# AirSensor_LoRA.net
KiCad netlist of a schematic drawn in EAGLE
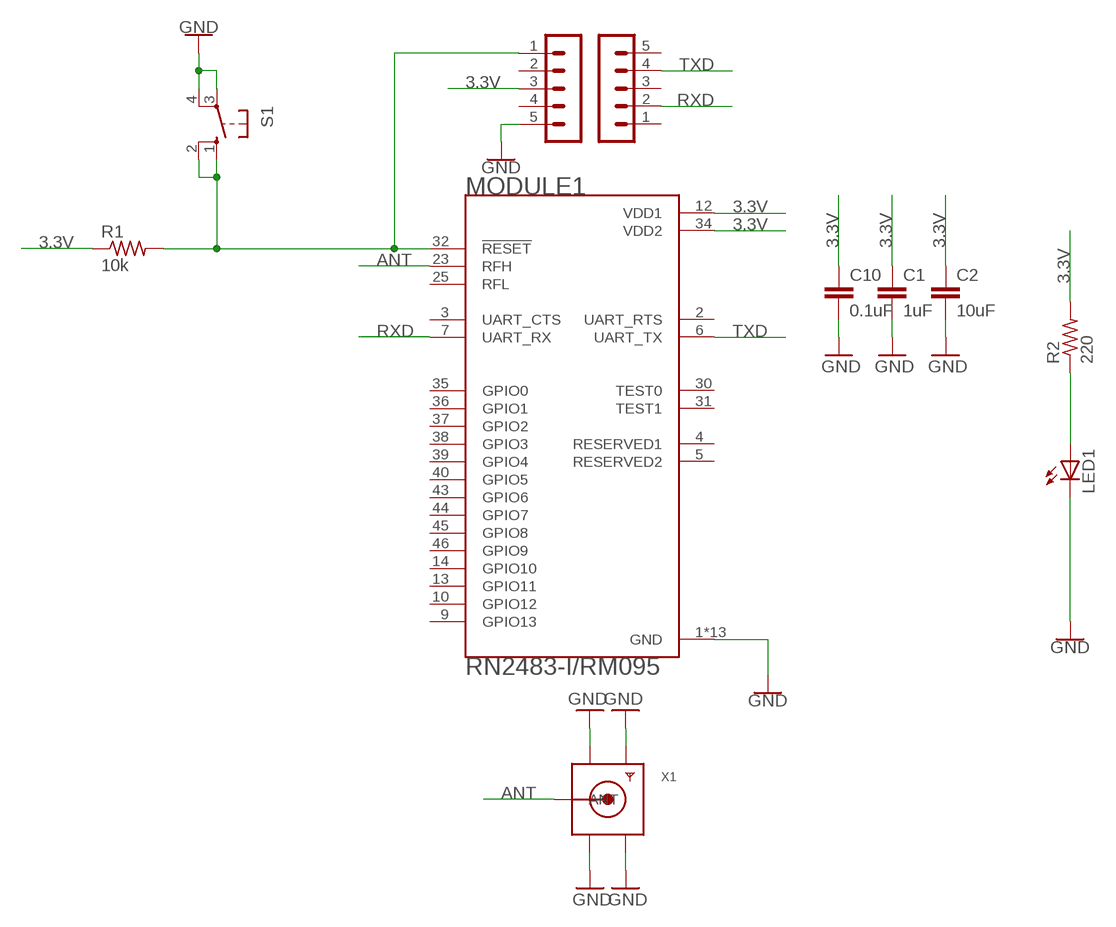
[diagram p0: schematic, sheet 1]

(export (version "E")
  (design (tool "Eeschema 10.0.6"))
  (components
    (comp (ref "C1")
      (value "1uF")
      (footprint "eagle-import:0805")
      (libsource (lib "eagle-import") (part "1.0UF-0805-25V-10%"))
    )
    (comp (ref "C2")
      (value "10uF")
      (footprint "eagle-import:0805")
      (libsource (lib "eagle-import") (part "1.0UF-0805-25V-10%"))
    )
    (comp (ref "C10")
      (value "0.1uF")
      (footprint "eagle-import:0805")
      (libsource (lib "eagle-import") (part "1.0UF-0805-25V-10%"))
    )
    (comp (ref "LED1")
      (value "LEDCHIPLED_0805")
      (footprint "eagle-import:CHIPLED_0805")
      (libsource (lib "eagle-import") (part "LEDCHIPLED_0805"))
    )
    (comp (ref "MODULE1")
      (value "RN2483-I/RM095")
      (footprint "eagle-import:MICROCHIP_RN2483-I_RM095")
      (fields (field (name "MF") "Microchip"))
      (libsource (lib "eagle-import") (part "RN2483-I/RM095"))
    )
    (comp (ref "R1")
      (value "10k")
      (footprint "eagle-import:RES_0805")
      (fields
        (field (name "DIGIKEY_PART_NUMBER") "541-0.0ATR-ND")
        (field (name "MANUFACTURER") "Vishay Dale")
        (field (name "MPN") "CRCW08050000Z0EA")
        (field (name "CREATED_BY") "PCBLayout.com")
      )
      (libsource (lib "eagle-import") (part "CRCW08050000Z0EA"))
    )
    (comp (ref "R2")
      (value "220")
      (footprint "eagle-import:RES_0805")
      (fields
        (field (name "DIGIKEY_PART_NUMBER") "541-0.0ATR-ND")
        (field (name "MANUFACTURER") "Vishay Dale")
        (field (name "MPN") "CRCW08050000Z0EA")
        (field (name "CREATED_BY") "PCBLayout.com")
      )
      (libsource (lib "eagle-import") (part "CRCW08050000Z0EA"))
    )
    (comp (ref "RFM95W_1")
      (value "LoRa_1")
      (footprint "eagle-import:MA05-1")
      (libsource (lib "eagle-import") (part "MA05-1"))
    )
    (comp (ref "RFM95W_2")
      (value "LoRa_2")
      (footprint "eagle-import:MA05-1")
      (libsource (lib "eagle-import") (part "MA05-1"))
    )
    (comp (ref "S1")
      (value "10-XX")
      (footprint "eagle-import:B3F-10XX")
      (fields (field (name "MPN") "B3F-1000"))
      (libsource (lib "eagle-import") (part "10-XX"))
    )
    (comp (ref "X1")
      (value "SMACONNECTOR_EDGE")
      (footprint "eagle-import:SMA_EDGELAUNCH")
      (libsource (lib "eagle-import") (part "SMACONNECTOR_EDGE"))
    )
  )
  (nets
    (net (code "1") (name "/3.3V") (class "Default")
      (node (ref "C1") (pin "1") (pinfunction "1_1") (pintype "passive"))
      (node (ref "C10") (pin "1") (pinfunction "1_1") (pintype "passive"))
      (node (ref "C2") (pin "1") (pinfunction "1_1") (pintype "passive"))
      (node (ref "MODULE1") (pin "12") (pinfunction "VDD1_12") (pintype "power_in"))
      (node (ref "MODULE1") (pin "34") (pinfunction "VDD2_34") (pintype "power_in"))
      (node (ref "R1") (pin "1") (pinfunction "1_1") (pintype "passive"))
      (node (ref "R2") (pin "2") (pinfunction "2_2") (pintype "passive"))
      (node (ref "RFM95W_1") (pin "3") (pinfunction "3_3") (pintype "passive"))
    )
    (net (code "2") (name "/ANT") (class "Default")
      (node (ref "MODULE1") (pin "23") (pinfunction "RFH_23") (pintype "input"))
      (node (ref "X1") (pin "P") (pinfunction "ANT_P") (pintype "bidirectional"))
    )
    (net (code "3") (name "/RXD") (class "Default")
      (node (ref "MODULE1") (pin "7") (pinfunction "UART_RX_7") (pintype "input"))
      (node (ref "RFM95W_2") (pin "2") (pinfunction "2_2") (pintype "passive"))
    )
    (net (code "4") (name "/TXD") (class "Default")
      (node (ref "MODULE1") (pin "6") (pinfunction "UART_TX_6") (pintype "output"))
      (node (ref "RFM95W_2") (pin "4") (pinfunction "4_4") (pintype "passive"))
    )
    (net (code "5") (name "GND") (class "Default")
      (node (ref "C1") (pin "2") (pinfunction "2_2") (pintype "passive"))
      (node (ref "C10") (pin "2") (pinfunction "2_2") (pintype "passive"))
      (node (ref "C2") (pin "2") (pinfunction "2_2") (pintype "passive"))
      (node (ref "LED1") (pin "C") (pinfunction "C_C") (pintype "passive"))
      (node (ref "MODULE1") (pin "1") (pinfunction "GND_1") (pintype "passive"))
      (node (ref "MODULE1") (pin "11") (pinfunction "GND_11") (pintype "passive"))
      (node (ref "MODULE1") (pin "20") (pinfunction "GND_20") (pintype "passive"))
      (node (ref "MODULE1") (pin "21") (pinfunction "GND_21") (pintype "passive"))
      (node (ref "MODULE1") (pin "22") (pinfunction "GND_22") (pintype "passive"))
      (node (ref "MODULE1") (pin "24") (pinfunction "GND_24") (pintype "passive"))
      (node (ref "MODULE1") (pin "26") (pinfunction "GND_26") (pintype "passive"))
      (node (ref "MODULE1") (pin "27") (pinfunction "GND_27") (pintype "passive"))
      (node (ref "MODULE1") (pin "28") (pinfunction "GND_28") (pintype "passive"))
      (node (ref "MODULE1") (pin "33") (pinfunction "GND_33") (pintype "passive"))
      (node (ref "MODULE1") (pin "41") (pinfunction "GND_41") (pintype "passive"))
      (node (ref "MODULE1") (pin "47") (pinfunction "GND_47") (pintype "passive"))
      (node (ref "MODULE1") (pin "8") (pinfunction "GND_8") (pintype "passive"))
      (node (ref "RFM95W_1") (pin "5") (pinfunction "5_5") (pintype "passive"))
      (node (ref "S1") (pin "3") (pinfunction "P_3") (pintype "passive"))
      (node (ref "S1") (pin "4") (pinfunction "P1_4") (pintype "passive"))
      (node (ref "X1") (pin "GND@1") (pinfunction "GND4_GND@1") (pintype "power_in"))
      (node (ref "X1") (pin "GND@2") (pinfunction "GND3_GND@2") (pintype "power_in"))
      (node (ref "X1") (pin "GND@3") (pinfunction "GND2_GND@3") (pintype "power_in"))
      (node (ref "X1") (pin "GND@4") (pinfunction "GND1_GND@4") (pintype "power_in"))
    )
    (net (code "6") (name "Net-(LED1-PadA)") (class "Default")
      (node (ref "LED1") (pin "A") (pinfunction "A_A") (pintype "passive"))
      (node (ref "R2") (pin "1") (pinfunction "1_1") (pintype "passive"))
    )
    (net (code "7") (name "Net-(MODULE1-~{RESET})") (class "Default")
      (node (ref "MODULE1") (pin "32") (pinfunction "~{RESET}_32") (pintype "input"))
      (node (ref "R1") (pin "2") (pinfunction "2_2") (pintype "passive"))
      (node (ref "RFM95W_1") (pin "1") (pinfunction "1_1") (pintype "passive"))
      (node (ref "S1") (pin "1") (pinfunction "S_1") (pintype "passive"))
      (node (ref "S1") (pin "2") (pinfunction "S1_2") (pintype "passive"))
    )
    (net (code "8") (name "unconnected-(MODULE1-GPIO0-Pad35)") (class "Default")
      (node (ref "MODULE1") (pin "35") (pinfunction "GPIO0_35") (pintype "bidirectional"))
    )
    (net (code "9") (name "unconnected-(MODULE1-GPIO1-Pad36)") (class "Default")
      (node (ref "MODULE1") (pin "36") (pinfunction "GPIO1_36") (pintype "bidirectional"))
    )
    (net (code "10") (name "unconnected-(MODULE1-GPIO2-Pad37)") (class "Default")
      (node (ref "MODULE1") (pin "37") (pinfunction "GPIO2_37") (pintype "bidirectional"))
    )
    (net (code "11") (name "unconnected-(MODULE1-GPIO3-Pad38)") (class "Default")
      (node (ref "MODULE1") (pin "38") (pinfunction "GPIO3_38") (pintype "bidirectional"))
    )
    (net (code "12") (name "unconnected-(MODULE1-GPIO4-Pad39)") (class "Default")
      (node (ref "MODULE1") (pin "39") (pinfunction "GPIO4_39") (pintype "bidirectional"))
    )
    (net (code "13") (name "unconnected-(MODULE1-GPIO5-Pad40)") (class "Default")
      (node (ref "MODULE1") (pin "40") (pinfunction "GPIO5_40") (pintype "bidirectional"))
    )
    (net (code "14") (name "unconnected-(MODULE1-GPIO6-Pad43)") (class "Default")
      (node (ref "MODULE1") (pin "43") (pinfunction "GPIO6_43") (pintype "bidirectional"))
    )
    (net (code "15") (name "unconnected-(MODULE1-GPIO7-Pad44)") (class "Default")
      (node (ref "MODULE1") (pin "44") (pinfunction "GPIO7_44") (pintype "bidirectional"))
    )
    (net (code "16") (name "unconnected-(MODULE1-GPIO8-Pad45)") (class "Default")
      (node (ref "MODULE1") (pin "45") (pinfunction "GPIO8_45") (pintype "bidirectional"))
    )
    (net (code "17") (name "unconnected-(MODULE1-GPIO9-Pad46)") (class "Default")
      (node (ref "MODULE1") (pin "46") (pinfunction "GPIO9_46") (pintype "bidirectional"))
    )
    (net (code "18") (name "unconnected-(MODULE1-GPIO10-Pad14)") (class "Default")
      (node (ref "MODULE1") (pin "14") (pinfunction "GPIO10_14") (pintype "bidirectional"))
    )
    (net (code "19") (name "unconnected-(MODULE1-GPIO11-Pad13)") (class "Default")
      (node (ref "MODULE1") (pin "13") (pinfunction "GPIO11_13") (pintype "bidirectional"))
    )
    (net (code "20") (name "unconnected-(MODULE1-GPIO12-Pad10)") (class "Default")
      (node (ref "MODULE1") (pin "10") (pinfunction "GPIO12_10") (pintype "bidirectional"))
    )
    (net (code "21") (name "unconnected-(MODULE1-GPIO13-Pad9)") (class "Default")
      (node (ref "MODULE1") (pin "9") (pinfunction "GPIO13_9") (pintype "bidirectional"))
    )
    (net (code "22") (name "unconnected-(MODULE1-RESERVED1-Pad4)") (class "Default")
      (node (ref "MODULE1") (pin "4") (pinfunction "RESERVED1_4") (pintype "passive"))
    )
    (net (code "23") (name "unconnected-(MODULE1-RESERVED2-Pad5)") (class "Default")
      (node (ref "MODULE1") (pin "5") (pinfunction "RESERVED2_5") (pintype "passive"))
    )
    (net (code "24") (name "unconnected-(MODULE1-RFL-Pad25)") (class "Default")
      (node (ref "MODULE1") (pin "25") (pinfunction "RFL_25") (pintype "input"))
    )
    (net (code "25") (name "unconnected-(MODULE1-TEST0-Pad30)") (class "Default")
      (node (ref "MODULE1") (pin "30") (pinfunction "TEST0_30") (pintype "passive"))
    )
    (net (code "26") (name "unconnected-(MODULE1-TEST1-Pad31)") (class "Default")
      (node (ref "MODULE1") (pin "31") (pinfunction "TEST1_31") (pintype "passive"))
    )
    (net (code "27") (name "unconnected-(MODULE1-UART_CTS-Pad3)") (class "Default")
      (node (ref "MODULE1") (pin "3") (pinfunction "UART_CTS_3") (pintype "input"))
    )
    (net (code "28") (name "unconnected-(MODULE1-UART_RTS-Pad2)") (class "Default")
      (node (ref "MODULE1") (pin "2") (pinfunction "UART_RTS_2") (pintype "output"))
    )
    (net (code "29") (name "unconnected-(RFM95W_1-Pad2)") (class "Default")
      (node (ref "RFM95W_1") (pin "2") (pinfunction "2_2") (pintype "passive"))
    )
    (net (code "30") (name "unconnected-(RFM95W_1-Pad4)") (class "Default")
      (node (ref "RFM95W_1") (pin "4") (pinfunction "4_4") (pintype "passive"))
    )
    (net (code "31") (name "unconnected-(RFM95W_2-Pad1)") (class "Default")
      (node (ref "RFM95W_2") (pin "1") (pinfunction "1_1") (pintype "passive"))
    )
    (net (code "32") (name "unconnected-(RFM95W_2-Pad3)") (class "Default")
      (node (ref "RFM95W_2") (pin "3") (pinfunction "3_3") (pintype "passive"))
    )
    (net (code "33") (name "unconnected-(RFM95W_2-Pad5)") (class "Default")
      (node (ref "RFM95W_2") (pin "5") (pinfunction "5_5") (pintype "passive"))
    )
  )
)
